# lab1_Eagle.net
KiCad netlist of a schematic drawn in EAGLE
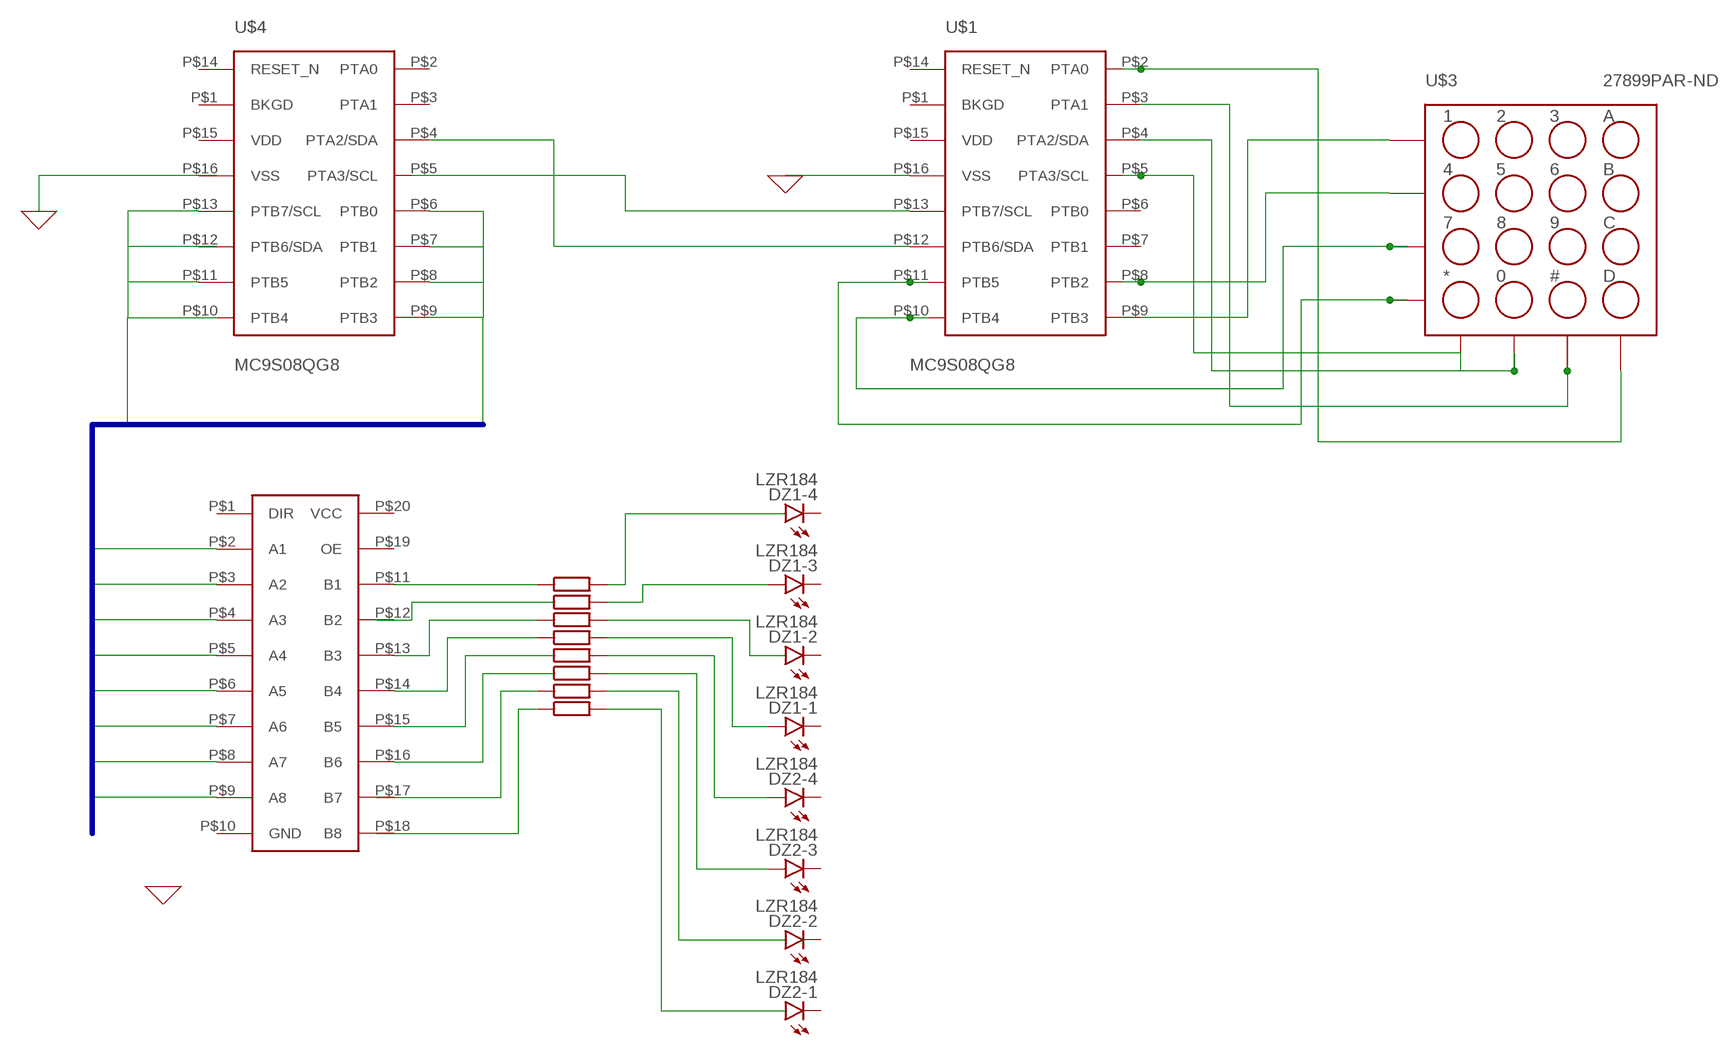
[diagram p0: schematic, sheet 1]

(export (version "E")
  (design (tool "Eeschema 10.0.6"))
  (components
    (comp (ref "DZ1")
      (value "LZR184")
      (footprint "eagle-import:LZR184")
      (libsource (lib "eagle-import") (part "LZR184"))
    )
    (comp (ref "DZ2")
      (value "LZR184")
      (footprint "eagle-import:LZR184")
      (libsource (lib "eagle-import") (part "LZR184"))
    )
    (comp (ref "U$1")
      (value "MC9S08QG8")
      (footprint "eagle-import:MC9S08QG8")
      (libsource (lib "eagle-import") (part "MC9S08QG8"))
    )
    (comp (ref "U$3")
      (value "27899PAR-ND")
      (footprint "eagle-import:27899PAR-ND")
      (libsource (lib "eagle-import") (part "27899PAR-ND"))
    )
    (comp (ref "U$4")
      (value "MC9S08QG8")
      (footprint "eagle-import:MC9S08QG8")
      (libsource (lib "eagle-import") (part "MC9S08QG8"))
    )
    (comp (ref "U$5")
      (value "SN74HC245")
      (footprint "eagle-import:SN74HC245")
      (libsource (lib "eagle-import") (part "SN74HC245"))
    )
  )
  (nets
    (net (code "1") (name "GND") (class "Default")
      (node (ref "U$1") (pin "P$16") (pinfunction "VSS_P$16") (pintype "bidirectional"))
    )
    (net (code "2") (name "Net-(U$1-PTA0)") (class "Default")
      (node (ref "U$1") (pin "P$2") (pinfunction "PTA0_P$2") (pintype "bidirectional"))
      (node (ref "U$3") (pin "P$5") (pinfunction "P$5_P$5") (pintype "bidirectional"))
    )
    (net (code "3") (name "Net-(U$1-PTA1)") (class "Default")
      (node (ref "U$1") (pin "P$3") (pinfunction "PTA1_P$3") (pintype "bidirectional"))
      (node (ref "U$3") (pin "P$6") (pinfunction "P$6_P$6") (pintype "bidirectional"))
    )
    (net (code "4") (name "Net-(U$1-PTA2{slash}SDA)") (class "Default")
      (node (ref "U$1") (pin "P$4") (pinfunction "PTA2/SDA_P$4") (pintype "bidirectional"))
      (node (ref "U$3") (pin "P$7") (pinfunction "P$7_P$7") (pintype "bidirectional"))
    )
    (net (code "5") (name "Net-(U$1-PTA3{slash}SCL)") (class "Default")
      (node (ref "U$1") (pin "P$5") (pinfunction "PTA3/SCL_P$5") (pintype "bidirectional"))
      (node (ref "U$3") (pin "P$8") (pinfunction "P$8_P$8") (pintype "bidirectional"))
    )
    (net (code "6") (name "Net-(U$1-PTB2)") (class "Default")
      (node (ref "U$1") (pin "P$8") (pinfunction "PTB2_P$8") (pintype "bidirectional"))
      (node (ref "U$3") (pin "P$2") (pinfunction "P$2_P$2") (pintype "bidirectional"))
    )
    (net (code "7") (name "Net-(U$1-PTB3)") (class "Default")
      (node (ref "U$1") (pin "P$9") (pinfunction "PTB3_P$9") (pintype "bidirectional"))
      (node (ref "U$3") (pin "P$1") (pinfunction "P$1_P$1") (pintype "bidirectional"))
    )
    (net (code "8") (name "Net-(U$1-PTB4)") (class "Default")
      (node (ref "U$1") (pin "P$10") (pinfunction "PTB4_P$10") (pintype "bidirectional"))
      (node (ref "U$3") (pin "P$3") (pinfunction "P$3_P$3") (pintype "bidirectional"))
    )
    (net (code "9") (name "Net-(U$1-PTB5)") (class "Default")
      (node (ref "U$1") (pin "P$11") (pinfunction "PTB5_P$11") (pintype "bidirectional"))
      (node (ref "U$3") (pin "P$4") (pinfunction "P$4_P$4") (pintype "bidirectional"))
    )
    (net (code "10") (name "Net-(U$1-PTB6{slash}SDA)") (class "Default")
      (node (ref "U$1") (pin "P$12") (pinfunction "PTB6/SDA_P$12") (pintype "bidirectional"))
      (node (ref "U$4") (pin "P$4") (pinfunction "PTA2/SDA_P$4") (pintype "bidirectional"))
    )
    (net (code "11") (name "Net-(U$4-PTB0)") (class "Default")
      (node (ref "U$4") (pin "P$6") (pinfunction "PTB0_P$6") (pintype "bidirectional"))
      (node (ref "U$4") (pin "P$7") (pinfunction "PTB1_P$7") (pintype "bidirectional"))
      (node (ref "U$4") (pin "P$8") (pinfunction "PTB2_P$8") (pintype "bidirectional"))
      (node (ref "U$4") (pin "P$9") (pinfunction "PTB3_P$9") (pintype "bidirectional"))
    )
    (net (code "12") (name "Net-(U$4-PTB5)") (class "Default")
      (node (ref "U$4") (pin "P$11") (pinfunction "PTB5_P$11") (pintype "bidirectional"))
      (node (ref "U$4") (pin "P$13") (pinfunction "PTB7/SCL_P$13") (pintype "bidirectional"))
    )
    (net (code "13") (name "unconnected-(DZ1A-A-PadA1)") (class "Default")
      (node (ref "DZ1") (pin "A1") (pinfunction "A_A1") (pintype "passive"))
    )
    (net (code "14") (name "unconnected-(DZ1A-C-PadK1)") (class "Default")
      (node (ref "DZ1") (pin "K1") (pinfunction "C_K1") (pintype "passive"))
    )
    (net (code "15") (name "unconnected-(DZ1B-A-PadA2)") (class "Default")
      (node (ref "DZ1") (pin "A2") (pinfunction "A_A2") (pintype "passive"))
    )
    (net (code "16") (name "unconnected-(DZ1B-C-PadK2)") (class "Default")
      (node (ref "DZ1") (pin "K2") (pinfunction "C_K2") (pintype "passive"))
    )
    (net (code "17") (name "unconnected-(DZ1C-A-PadA3)") (class "Default")
      (node (ref "DZ1") (pin "A3") (pinfunction "A_A3") (pintype "passive"))
    )
    (net (code "18") (name "unconnected-(DZ1C-C-PadK3)") (class "Default")
      (node (ref "DZ1") (pin "K3") (pinfunction "C_K3") (pintype "passive"))
    )
    (net (code "19") (name "unconnected-(DZ1D-A-PadA4)") (class "Default")
      (node (ref "DZ1") (pin "A4") (pinfunction "A_A4") (pintype "passive"))
    )
    (net (code "20") (name "unconnected-(DZ1D-C-PadK4)") (class "Default")
      (node (ref "DZ1") (pin "K4") (pinfunction "C_K4") (pintype "passive"))
    )
    (net (code "21") (name "unconnected-(DZ2A-A-PadA1)") (class "Default")
      (node (ref "DZ2") (pin "A1") (pinfunction "A_A1") (pintype "passive"))
    )
    (net (code "22") (name "unconnected-(DZ2A-C-PadK1)") (class "Default")
      (node (ref "DZ2") (pin "K1") (pinfunction "C_K1") (pintype "passive"))
    )
    (net (code "23") (name "unconnected-(DZ2B-A-PadA2)") (class "Default")
      (node (ref "DZ2") (pin "A2") (pinfunction "A_A2") (pintype "passive"))
    )
    (net (code "24") (name "unconnected-(DZ2B-C-PadK2)") (class "Default")
      (node (ref "DZ2") (pin "K2") (pinfunction "C_K2") (pintype "passive"))
    )
    (net (code "25") (name "unconnected-(DZ2C-A-PadA3)") (class "Default")
      (node (ref "DZ2") (pin "A3") (pinfunction "A_A3") (pintype "passive"))
    )
    (net (code "26") (name "unconnected-(DZ2C-C-PadK3)") (class "Default")
      (node (ref "DZ2") (pin "K3") (pinfunction "C_K3") (pintype "passive"))
    )
    (net (code "27") (name "unconnected-(DZ2D-A-PadA4)") (class "Default")
      (node (ref "DZ2") (pin "A4") (pinfunction "A_A4") (pintype "passive"))
    )
    (net (code "28") (name "unconnected-(DZ2D-C-PadK4)") (class "Default")
      (node (ref "DZ2") (pin "K4") (pinfunction "C_K4") (pintype "passive"))
    )
    (net (code "29") (name "unconnected-(U$1-BKGD-PadP$1)") (class "Default")
      (node (ref "U$1") (pin "P$1") (pinfunction "BKGD_P$1") (pintype "bidirectional"))
    )
    (net (code "30") (name "unconnected-(U$1-PTB0-PadP$6)") (class "Default")
      (node (ref "U$1") (pin "P$6") (pinfunction "PTB0_P$6") (pintype "bidirectional"))
    )
    (net (code "31") (name "unconnected-(U$1-PTB1-PadP$7)") (class "Default")
      (node (ref "U$1") (pin "P$7") (pinfunction "PTB1_P$7") (pintype "bidirectional"))
    )
    (net (code "32") (name "unconnected-(U$1-PTB7{slash}SCL-PadP$13)") (class "Default")
      (node (ref "U$1") (pin "P$13") (pinfunction "PTB7/SCL_P$13") (pintype "bidirectional"))
    )
    (net (code "33") (name "unconnected-(U$1-RESET_N-PadP$14)") (class "Default")
      (node (ref "U$1") (pin "P$14") (pinfunction "RESET_N_P$14") (pintype "bidirectional"))
    )
    (net (code "34") (name "unconnected-(U$1-VDD-PadP$15)") (class "Default")
      (node (ref "U$1") (pin "P$15") (pinfunction "VDD_P$15") (pintype "bidirectional"))
    )
    (net (code "35") (name "unconnected-(U$4-BKGD-PadP$1)") (class "Default")
      (node (ref "U$4") (pin "P$1") (pinfunction "BKGD_P$1") (pintype "bidirectional"))
    )
    (net (code "36") (name "unconnected-(U$4-PTA0-PadP$2)") (class "Default")
      (node (ref "U$4") (pin "P$2") (pinfunction "PTA0_P$2") (pintype "bidirectional"))
    )
    (net (code "37") (name "unconnected-(U$4-PTA1-PadP$3)") (class "Default")
      (node (ref "U$4") (pin "P$3") (pinfunction "PTA1_P$3") (pintype "bidirectional"))
    )
    (net (code "38") (name "unconnected-(U$4-PTA3{slash}SCL-PadP$5)") (class "Default")
      (node (ref "U$4") (pin "P$5") (pinfunction "PTA3/SCL_P$5") (pintype "bidirectional"))
    )
    (net (code "39") (name "unconnected-(U$4-PTB4-PadP$10)") (class "Default")
      (node (ref "U$4") (pin "P$10") (pinfunction "PTB4_P$10") (pintype "bidirectional"))
    )
    (net (code "40") (name "unconnected-(U$4-PTB6{slash}SDA-PadP$12)") (class "Default")
      (node (ref "U$4") (pin "P$12") (pinfunction "PTB6/SDA_P$12") (pintype "bidirectional"))
    )
    (net (code "41") (name "unconnected-(U$4-RESET_N-PadP$14)") (class "Default")
      (node (ref "U$4") (pin "P$14") (pinfunction "RESET_N_P$14") (pintype "bidirectional"))
    )
    (net (code "42") (name "unconnected-(U$4-VDD-PadP$15)") (class "Default")
      (node (ref "U$4") (pin "P$15") (pinfunction "VDD_P$15") (pintype "bidirectional"))
    )
    (net (code "43") (name "unconnected-(U$4-VSS-PadP$16)") (class "Default")
      (node (ref "U$4") (pin "P$16") (pinfunction "VSS_P$16") (pintype "bidirectional"))
    )
    (net (code "44") (name "unconnected-(U$5-A1-PadP$2)") (class "Default")
      (node (ref "U$5") (pin "P$2") (pinfunction "A1_P$2") (pintype "bidirectional"))
    )
    (net (code "45") (name "unconnected-(U$5-A2-PadP$3)") (class "Default")
      (node (ref "U$5") (pin "P$3") (pinfunction "A2_P$3") (pintype "bidirectional"))
    )
    (net (code "46") (name "unconnected-(U$5-A3-PadP$4)") (class "Default")
      (node (ref "U$5") (pin "P$4") (pinfunction "A3_P$4") (pintype "bidirectional"))
    )
    (net (code "47") (name "unconnected-(U$5-A4-PadP$5)") (class "Default")
      (node (ref "U$5") (pin "P$5") (pinfunction "A4_P$5") (pintype "bidirectional"))
    )
    (net (code "48") (name "unconnected-(U$5-A5-PadP$6)") (class "Default")
      (node (ref "U$5") (pin "P$6") (pinfunction "A5_P$6") (pintype "bidirectional"))
    )
    (net (code "49") (name "unconnected-(U$5-A6-PadP$7)") (class "Default")
      (node (ref "U$5") (pin "P$7") (pinfunction "A6_P$7") (pintype "bidirectional"))
    )
    (net (code "50") (name "unconnected-(U$5-A7-PadP$8)") (class "Default")
      (node (ref "U$5") (pin "P$8") (pinfunction "A7_P$8") (pintype "bidirectional"))
    )
    (net (code "51") (name "unconnected-(U$5-A8-PadP$9)") (class "Default")
      (node (ref "U$5") (pin "P$9") (pinfunction "A8_P$9") (pintype "bidirectional"))
    )
    (net (code "52") (name "unconnected-(U$5-B1-PadP$11)") (class "Default")
      (node (ref "U$5") (pin "P$11") (pinfunction "B1_P$11") (pintype "bidirectional"))
    )
    (net (code "53") (name "unconnected-(U$5-B2-PadP$12)") (class "Default")
      (node (ref "U$5") (pin "P$12") (pinfunction "B2_P$12") (pintype "bidirectional"))
    )
    (net (code "54") (name "unconnected-(U$5-B3-PadP$13)") (class "Default")
      (node (ref "U$5") (pin "P$13") (pinfunction "B3_P$13") (pintype "bidirectional"))
    )
    (net (code "55") (name "unconnected-(U$5-B4-PadP$14)") (class "Default")
      (node (ref "U$5") (pin "P$14") (pinfunction "B4_P$14") (pintype "bidirectional"))
    )
    (net (code "56") (name "unconnected-(U$5-B5-PadP$15)") (class "Default")
      (node (ref "U$5") (pin "P$15") (pinfunction "B5_P$15") (pintype "bidirectional"))
    )
    (net (code "57") (name "unconnected-(U$5-B6-PadP$16)") (class "Default")
      (node (ref "U$5") (pin "P$16") (pinfunction "B6_P$16") (pintype "bidirectional"))
    )
    (net (code "58") (name "unconnected-(U$5-B7-PadP$17)") (class "Default")
      (node (ref "U$5") (pin "P$17") (pinfunction "B7_P$17") (pintype "bidirectional"))
    )
    (net (code "59") (name "unconnected-(U$5-B8-PadP$18)") (class "Default")
      (node (ref "U$5") (pin "P$18") (pinfunction "B8_P$18") (pintype "bidirectional"))
    )
    (net (code "60") (name "unconnected-(U$5-DIR-PadP$1)") (class "Default")
      (node (ref "U$5") (pin "P$1") (pinfunction "DIR_P$1") (pintype "bidirectional"))
    )
    (net (code "61") (name "unconnected-(U$5-GND-PadP$10)") (class "Default")
      (node (ref "U$5") (pin "P$10") (pinfunction "GND_P$10") (pintype "bidirectional"))
    )
    (net (code "62") (name "unconnected-(U$5-OE-PadP$19)") (class "Default")
      (node (ref "U$5") (pin "P$19") (pinfunction "OE_P$19") (pintype "bidirectional"))
    )
    (net (code "63") (name "unconnected-(U$5-VCC-PadP$20)") (class "Default")
      (node (ref "U$5") (pin "P$20") (pinfunction "VCC_P$20") (pintype "bidirectional"))
    )
  )
)
